# Naze32.net
KiCad netlist of a schematic drawn in EAGLE
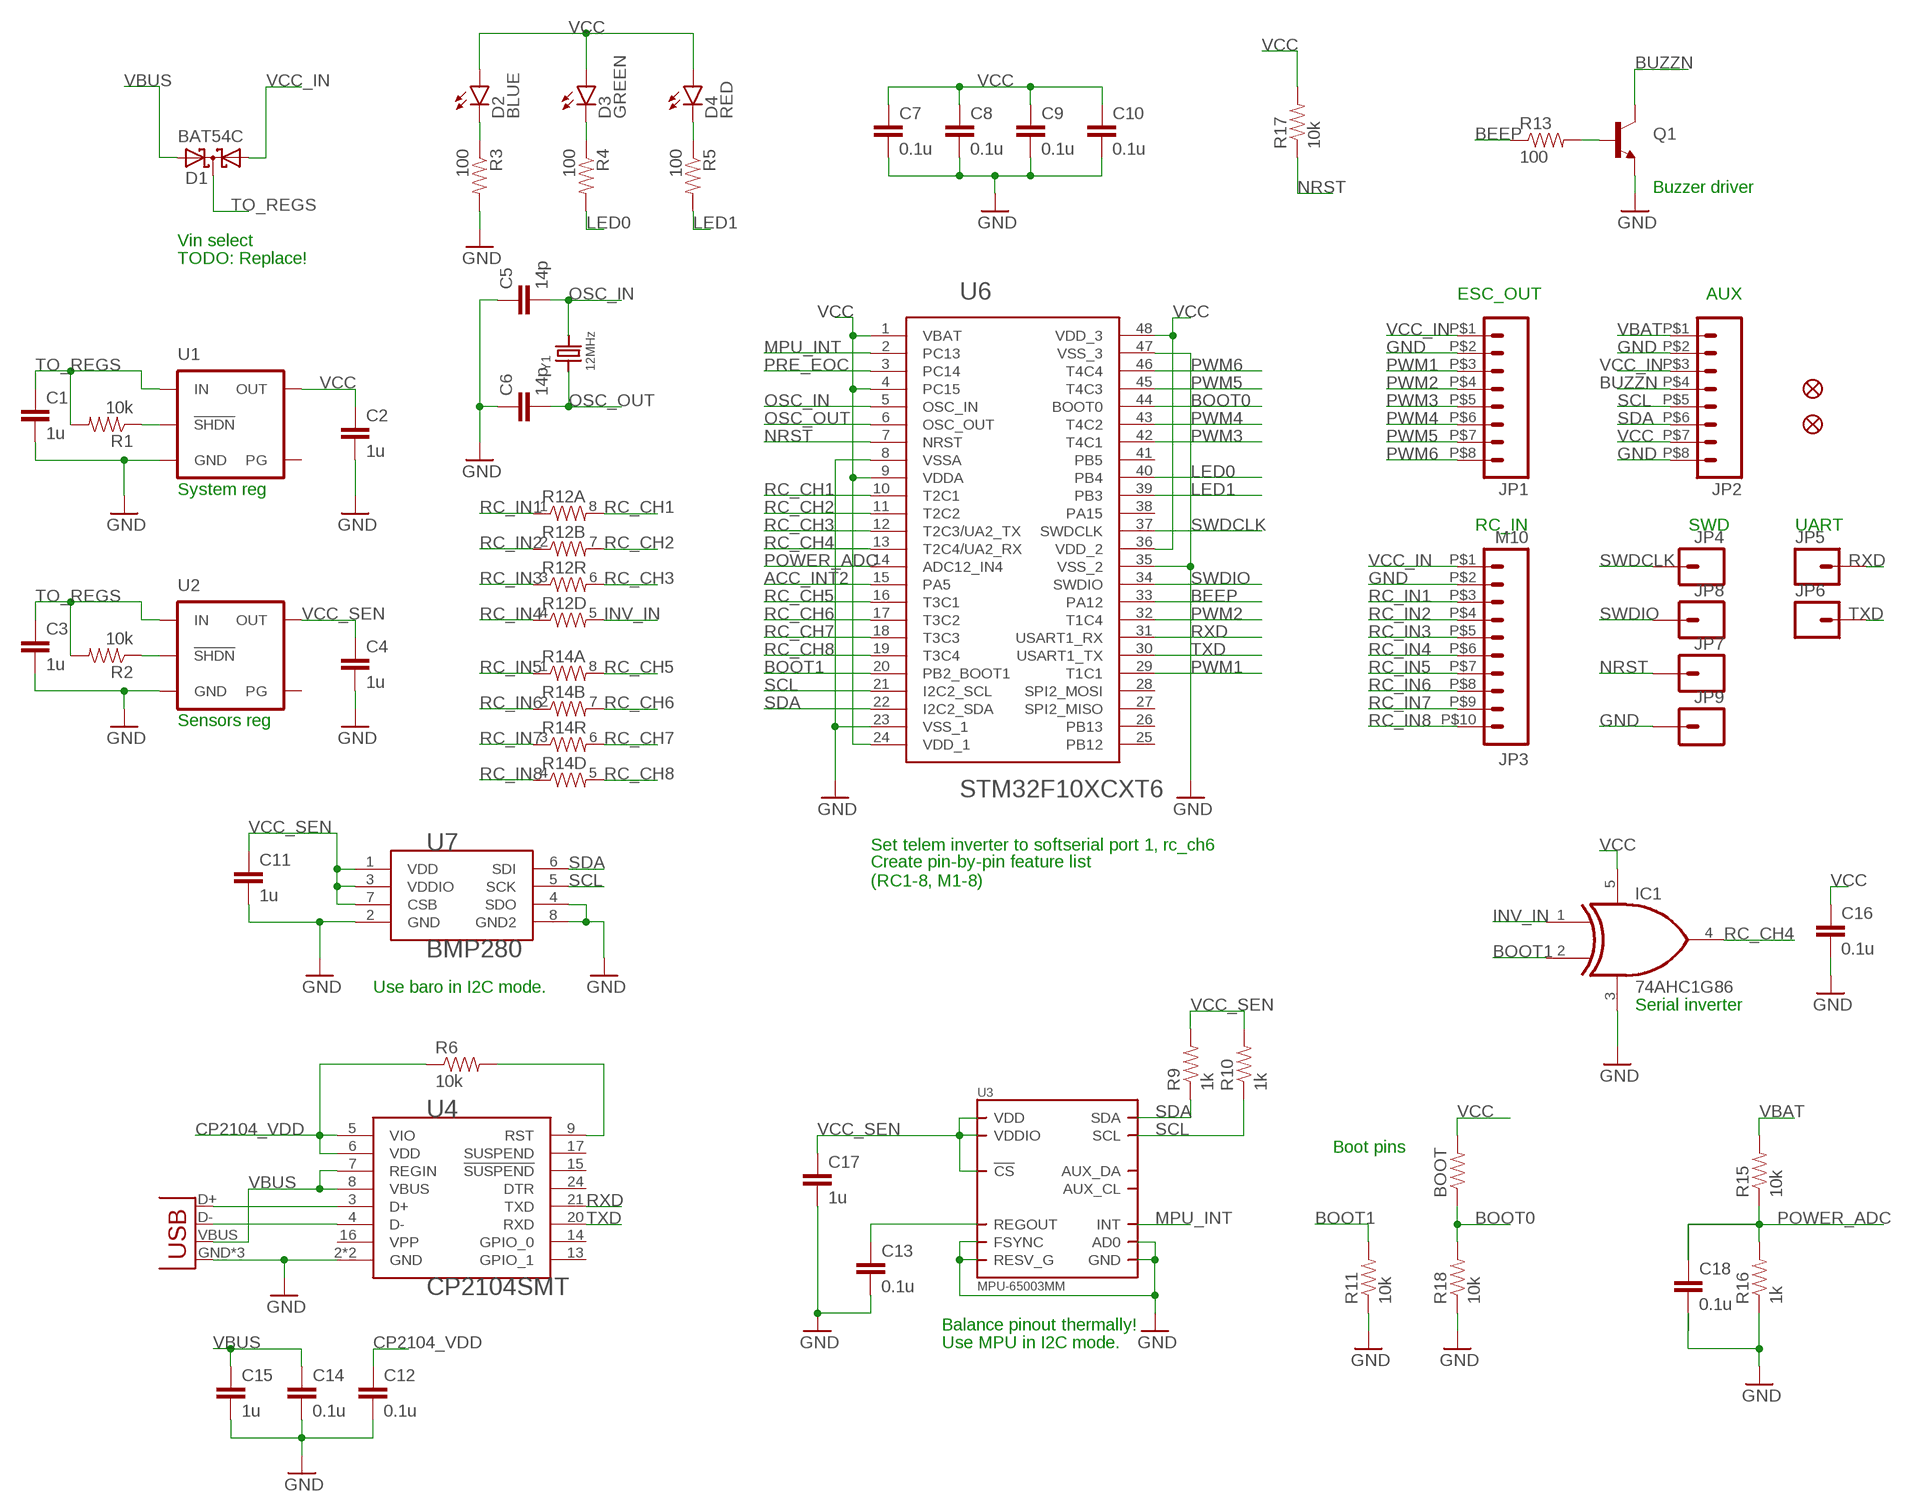
[diagram p0: schematic, sheet 1]

(export (version "E")
  (design (tool "Eeschema 10.0.6"))
  (components
    (comp (ref "BOOT")
      (value "RESISTOR0603")
      (footprint "eagle-import:0603-RES")
      (libsource (lib "eagle-import") (part "RESISTOR0603"))
    )
    (comp (ref "C1")
      (value "1u")
      (footprint "eagle-import:0402-CAP")
      (libsource (lib "eagle-import") (part "CAP0402-CAP"))
    )
    (comp (ref "C2")
      (value "1u")
      (footprint "eagle-import:0402-CAP")
      (libsource (lib "eagle-import") (part "CAP0402-CAP"))
    )
    (comp (ref "C3")
      (value "1u")
      (footprint "eagle-import:0402-CAP")
      (libsource (lib "eagle-import") (part "CAP0402-CAP"))
    )
    (comp (ref "C4")
      (value "1u")
      (footprint "eagle-import:0402-CAP")
      (libsource (lib "eagle-import") (part "CAP0402-CAP"))
    )
    (comp (ref "C5")
      (value "14p")
      (footprint "eagle-import:0402-CAP")
      (libsource (lib "eagle-import") (part "CAP0402-CAP"))
    )
    (comp (ref "C6")
      (value "14p")
      (footprint "eagle-import:0402-CAP")
      (libsource (lib "eagle-import") (part "CAP0402-CAP"))
    )
    (comp (ref "C7")
      (value "0.1u")
      (footprint "eagle-import:0402-CAP")
      (libsource (lib "eagle-import") (part "CAP0402-CAP"))
    )
    (comp (ref "C8")
      (value "0.1u")
      (footprint "eagle-import:0402-CAP")
      (libsource (lib "eagle-import") (part "CAP0402-CAP"))
    )
    (comp (ref "C9")
      (value "0.1u")
      (footprint "eagle-import:0402-CAP")
      (libsource (lib "eagle-import") (part "CAP0402-CAP"))
    )
    (comp (ref "C10")
      (value "0.1u")
      (footprint "eagle-import:0402-CAP")
      (libsource (lib "eagle-import") (part "CAP0402-CAP"))
    )
    (comp (ref "C11")
      (value "1u")
      (footprint "eagle-import:0402-CAP")
      (libsource (lib "eagle-import") (part "CAP0402-CAP"))
    )
    (comp (ref "C12")
      (value "0.1u")
      (footprint "eagle-import:0402-CAP")
      (libsource (lib "eagle-import") (part "CAP0402-CAP"))
    )
    (comp (ref "C13")
      (value "0.1u")
      (footprint "eagle-import:0402-CAP")
      (libsource (lib "eagle-import") (part "CAP0402-CAP"))
    )
    (comp (ref "C14")
      (value "0.1u")
      (footprint "eagle-import:0402-CAP")
      (libsource (lib "eagle-import") (part "CAP0402-CAP"))
    )
    (comp (ref "C15")
      (value "1u")
      (footprint "eagle-import:0402-CAP")
      (libsource (lib "eagle-import") (part "CAP0402-CAP"))
    )
    (comp (ref "C16")
      (value "0.1u")
      (footprint "eagle-import:0402-CAP")
      (libsource (lib "eagle-import") (part "CAP0402-CAP"))
    )
    (comp (ref "C17")
      (value "1u")
      (footprint "eagle-import:0402-CAP")
      (libsource (lib "eagle-import") (part "CAP0402-CAP"))
    )
    (comp (ref "C18")
      (value "0.1u")
      (footprint "eagle-import:0402-CAP")
      (libsource (lib "eagle-import") (part "CAP0402-CAP"))
    )
    (comp (ref "D1")
      (value "BAT54C")
      (footprint "eagle-import:SOT23")
      (libsource (lib "eagle-import") (part "BAT54C"))
    )
    (comp (ref "D2")
      (value "BLUE")
      (footprint "eagle-import:LED-0603")
      (libsource (lib "eagle-import") (part "LED-BLUE0603"))
    )
    (comp (ref "D3")
      (value "GREEN")
      (footprint "eagle-import:LED-0603")
      (libsource (lib "eagle-import") (part "LED-GREEN0603"))
    )
    (comp (ref "D4")
      (value "RED")
      (footprint "eagle-import:LED-0603")
      (libsource (lib "eagle-import") (part "LED-RED0603"))
    )
    (comp (ref "FID1")
      (value "FIDUCIALUFIDUCIAL")
      (footprint "eagle-import:MICRO-FIDUCIAL")
      (libsource (lib "eagle-import") (part "FIDUCIALUFIDUCIAL"))
    )
    (comp (ref "FID2")
      (value "FIDUCIALUFIDUCIAL")
      (footprint "eagle-import:MICRO-FIDUCIAL")
      (libsource (lib "eagle-import") (part "FIDUCIALUFIDUCIAL"))
    )
    (comp (ref "IC1")
      (value "74AHC1G86")
      (footprint "eagle-import:SC70-5")
      (libsource (lib "eagle-import") (part "741G86DCKAHC"))
    )
    (comp (ref "J1")
      (value "USB-MICROB")
      (footprint "eagle-import:USB-MICROB")
      (libsource (lib "eagle-import") (part "USB-MICROB"))
    )
    (comp (ref "JP1")
      (value "M08PAD-1X8")
      (footprint "eagle-import:PAD-1X8")
      (libsource (lib "eagle-import") (part "M08PAD-1X8"))
    )
    (comp (ref "JP2")
      (value "M08PAD-1X8")
      (footprint "eagle-import:PAD-1X8")
      (libsource (lib "eagle-import") (part "M08PAD-1X8"))
    )
    (comp (ref "JP3")
      (value "M10")
      (footprint "eagle-import:PAD_1X10")
      (libsource (lib "eagle-import") (part "M10"))
    )
    (comp (ref "JP4")
      (value "SCK")
      (footprint "eagle-import:PAD-ROUND")
      (libsource (lib "eagle-import") (part "M01ROUND"))
    )
    (comp (ref "JP5")
      (value "RX")
      (footprint "eagle-import:PAD-ROUND")
      (libsource (lib "eagle-import") (part "M01ROUND"))
    )
    (comp (ref "JP6")
      (value "TX")
      (footprint "eagle-import:PAD-ROUND")
      (libsource (lib "eagle-import") (part "M01ROUND"))
    )
    (comp (ref "JP7")
      (value "RST")
      (footprint "eagle-import:PAD-ROUND")
      (libsource (lib "eagle-import") (part "M01ROUND"))
    )
    (comp (ref "JP8")
      (value "IO")
      (footprint "eagle-import:PAD-ROUND")
      (libsource (lib "eagle-import") (part "M01ROUND"))
    )
    (comp (ref "JP9")
      (value "GND")
      (footprint "eagle-import:PAD-ROUND")
      (libsource (lib "eagle-import") (part "M01ROUND"))
    )
    (comp (ref "Q1")
      (value "TRANSISTOR_NPNSOT23")
      (footprint "eagle-import:SOT23")
      (libsource (lib "eagle-import") (part "TRANSISTOR_NPNSOT23"))
    )
    (comp (ref "R1")
      (value "10k")
      (footprint "eagle-import:0402-RES")
      (libsource (lib "eagle-import") (part "RESISTOR"))
    )
    (comp (ref "R2")
      (value "10k")
      (footprint "eagle-import:0402-RES")
      (libsource (lib "eagle-import") (part "RESISTOR"))
    )
    (comp (ref "R3")
      (value "100")
      (footprint "eagle-import:0402-RES")
      (libsource (lib "eagle-import") (part "RESISTOR"))
    )
    (comp (ref "R4")
      (value "100")
      (footprint "eagle-import:0402-RES")
      (libsource (lib "eagle-import") (part "RESISTOR"))
    )
    (comp (ref "R5")
      (value "100")
      (footprint "eagle-import:0402-RES")
      (libsource (lib "eagle-import") (part "RESISTOR"))
    )
    (comp (ref "R6")
      (value "10k")
      (footprint "eagle-import:0402-RES")
      (libsource (lib "eagle-import") (part "RESISTOR"))
    )
    (comp (ref "R9")
      (value "1k")
      (footprint "eagle-import:0402-RES")
      (libsource (lib "eagle-import") (part "RESISTOR"))
    )
    (comp (ref "R10")
      (value "1k")
      (footprint "eagle-import:0402-RES")
      (libsource (lib "eagle-import") (part "RESISTOR"))
    )
    (comp (ref "R11")
      (value "10k")
      (footprint "eagle-import:0402-RES")
      (libsource (lib "eagle-import") (part "RESISTOR"))
    )
    (comp (ref "R12")
      (value "RESISTOR-ARRAY0603-ARV")
      (footprint "eagle-import:0603-ARV")
      (libsource (lib "eagle-import") (part "RESISTOR-ARRAY0603-ARV"))
    )
    (comp (ref "R13")
      (value "100")
      (footprint "eagle-import:0402-RES")
      (libsource (lib "eagle-import") (part "RESISTOR"))
    )
    (comp (ref "R14")
      (value "RESISTOR-ARRAY0603-ARV")
      (footprint "eagle-import:0603-ARV")
      (libsource (lib "eagle-import") (part "RESISTOR-ARRAY0603-ARV"))
    )
    (comp (ref "R15")
      (value "10k")
      (footprint "eagle-import:0402-RES")
      (libsource (lib "eagle-import") (part "RESISTOR"))
    )
    (comp (ref "R16")
      (value "1k")
      (footprint "eagle-import:0402-RES")
      (libsource (lib "eagle-import") (part "RESISTOR"))
    )
    (comp (ref "R17")
      (value "10k")
      (footprint "eagle-import:0402-RES")
      (libsource (lib "eagle-import") (part "RESISTOR"))
    )
    (comp (ref "R18")
      (value "10k")
      (footprint "eagle-import:0402-RES")
      (libsource (lib "eagle-import") (part "RESISTOR"))
    )
    (comp (ref "U1")
      (value "MCP18243.3V")
      (footprint "eagle-import:SOT23-5")
      (libsource (lib "eagle-import") (part "MCP18243.3V"))
    )
    (comp (ref "U2")
      (value "MCP18243.3V")
      (footprint "eagle-import:SOT23-5")
      (libsource (lib "eagle-import") (part "MCP18243.3V"))
    )
    (comp (ref "U3")
      (value "MPU-65003MM")
      (footprint "eagle-import:QFN-24_3X3")
      (libsource (lib "eagle-import") (part "MPU-65003MM"))
    )
    (comp (ref "U4")
      (value "CP2104SMT")
      (footprint "eagle-import:QFN-24_ALT2")
      (libsource (lib "eagle-import") (part "CP2104SMT"))
    )
    (comp (ref "U6")
      (value "STM32F10XCXT6")
      (footprint "eagle-import:TQFP48")
      (libsource (lib "eagle-import") (part "STM32F10XCXT6"))
    )
    (comp (ref "U7")
      (value "BMP280")
      (footprint "eagle-import:LGA8")
      (libsource (lib "eagle-import") (part "BMP280"))
    )
    (comp (ref "Y1")
      (value "12MHz")
      (footprint "eagle-import:3.2X2.5MM")
      (libsource (lib "eagle-import") (part "CRYSTAL.3.2X2.5MM"))
    )
  )
  (nets
    (net (code "1") (name "/ACC_INT2") (class "Default")
      (node (ref "U6") (pin "15") (pinfunction "PA5_15") (pintype "bidirectional"))
    )
    (net (code "2") (name "/BEEP") (class "Default")
      (node (ref "R13") (pin "1") (pinfunction "1_1") (pintype "passive"))
      (node (ref "U6") (pin "33") (pinfunction "PA12_33") (pintype "bidirectional"))
    )
    (net (code "3") (name "/BOOT0") (class "Default")
      (node (ref "BOOT") (pin "1") (pinfunction "1_1") (pintype "passive"))
      (node (ref "R18") (pin "2") (pinfunction "2_2") (pintype "passive"))
      (node (ref "U6") (pin "44") (pinfunction "BOOT0_44") (pintype "bidirectional"))
    )
    (net (code "4") (name "/BOOT1") (class "Default")
      (node (ref "IC1") (pin "2") (pinfunction "I1_2") (pintype "input"))
      (node (ref "R11") (pin "2") (pinfunction "2_2") (pintype "passive"))
      (node (ref "U6") (pin "20") (pinfunction "PB2_BOOT1_20") (pintype "bidirectional"))
    )
    (net (code "5") (name "/BUZZN") (class "Default")
      (node (ref "JP2") (pin "P$4") (pinfunction "4_P$4") (pintype "passive"))
      (node (ref "Q1") (pin "3") (pinfunction "C_3") (pintype "passive"))
    )
    (net (code "6") (name "/CP2104_VDD") (class "Default")
      (node (ref "C12") (pin "1") (pinfunction "1_1") (pintype "passive"))
      (node (ref "R6") (pin "1") (pinfunction "1_1") (pintype "passive"))
      (node (ref "U4") (pin "5") (pinfunction "VIO_5") (pintype "bidirectional"))
      (node (ref "U4") (pin "6") (pinfunction "VDD_6") (pintype "bidirectional"))
    )
    (net (code "7") (name "/INV_IN") (class "Default")
      (node (ref "IC1") (pin "1") (pinfunction "I0_1") (pintype "input"))
      (node (ref "R12") (pin "5") (pinfunction "2_5") (pintype "passive"))
    )
    (net (code "8") (name "/LED0") (class "Default")
      (node (ref "R4") (pin "2") (pinfunction "2_2") (pintype "passive"))
      (node (ref "U6") (pin "40") (pinfunction "PB4_40") (pintype "bidirectional"))
    )
    (net (code "9") (name "/LED1") (class "Default")
      (node (ref "R5") (pin "2") (pinfunction "2_2") (pintype "passive"))
      (node (ref "U6") (pin "39") (pinfunction "PB3_39") (pintype "bidirectional"))
    )
    (net (code "10") (name "/MPU_INT") (class "Default")
      (node (ref "U3") (pin "12") (pinfunction "INT_12") (pintype "bidirectional"))
      (node (ref "U6") (pin "2") (pinfunction "PC13_2") (pintype "bidirectional"))
    )
    (net (code "11") (name "/NRST") (class "Default")
      (node (ref "JP7") (pin "P$1") (pinfunction "1_P$1") (pintype "passive"))
      (node (ref "R17") (pin "1") (pinfunction "1_1") (pintype "passive"))
      (node (ref "U6") (pin "7") (pinfunction "NRST_7") (pintype "bidirectional"))
    )
    (net (code "12") (name "/OSC_IN") (class "Default")
      (node (ref "C5") (pin "2") (pinfunction "2_2") (pintype "passive"))
      (node (ref "U6") (pin "5") (pinfunction "OSC_IN_5") (pintype "bidirectional"))
      (node (ref "Y1") (pin "3") (pinfunction "2_3") (pintype "passive"))
    )
    (net (code "13") (name "/OSC_OUT") (class "Default")
      (node (ref "C6") (pin "2") (pinfunction "2_2") (pintype "passive"))
      (node (ref "U6") (pin "6") (pinfunction "OSC_OUT_6") (pintype "bidirectional"))
      (node (ref "Y1") (pin "1") (pinfunction "1_1") (pintype "passive"))
    )
    (net (code "14") (name "/POWER_ADC") (class "Default")
      (node (ref "C18") (pin "1") (pinfunction "1_1") (pintype "passive"))
      (node (ref "R15") (pin "1") (pinfunction "1_1") (pintype "passive"))
      (node (ref "R16") (pin "2") (pinfunction "2_2") (pintype "passive"))
      (node (ref "U6") (pin "14") (pinfunction "ADC12_IN4_14") (pintype "bidirectional"))
    )
    (net (code "15") (name "/PRE_EOC") (class "Default")
      (node (ref "U6") (pin "3") (pinfunction "PC14_3") (pintype "bidirectional"))
    )
    (net (code "16") (name "/PWM1") (class "Default")
      (node (ref "JP1") (pin "P$3") (pinfunction "3_P$3") (pintype "passive"))
      (node (ref "U6") (pin "29") (pinfunction "T1C1_29") (pintype "bidirectional"))
    )
    (net (code "17") (name "/PWM2") (class "Default")
      (node (ref "JP1") (pin "P$4") (pinfunction "4_P$4") (pintype "passive"))
      (node (ref "U6") (pin "32") (pinfunction "T1C4_32") (pintype "bidirectional"))
    )
    (net (code "18") (name "/PWM3") (class "Default")
      (node (ref "JP1") (pin "P$5") (pinfunction "5_P$5") (pintype "passive"))
      (node (ref "U6") (pin "42") (pinfunction "T4C1_42") (pintype "bidirectional"))
    )
    (net (code "19") (name "/PWM4") (class "Default")
      (node (ref "JP1") (pin "P$6") (pinfunction "6_P$6") (pintype "passive"))
      (node (ref "U6") (pin "43") (pinfunction "T4C2_43") (pintype "bidirectional"))
    )
    (net (code "20") (name "/PWM5") (class "Default")
      (node (ref "JP1") (pin "P$7") (pinfunction "7_P$7") (pintype "passive"))
      (node (ref "U6") (pin "45") (pinfunction "T4C3_45") (pintype "bidirectional"))
    )
    (net (code "21") (name "/PWM6") (class "Default")
      (node (ref "JP1") (pin "P$8") (pinfunction "8_P$8") (pintype "passive"))
      (node (ref "U6") (pin "46") (pinfunction "T4C4_46") (pintype "bidirectional"))
    )
    (net (code "22") (name "/RC_CH1") (class "Default")
      (node (ref "R12") (pin "8") (pinfunction "2_8") (pintype "passive"))
      (node (ref "U6") (pin "10") (pinfunction "T2C1_10") (pintype "bidirectional"))
    )
    (net (code "23") (name "/RC_CH2") (class "Default")
      (node (ref "R12") (pin "7") (pinfunction "2_7") (pintype "passive"))
      (node (ref "U6") (pin "11") (pinfunction "T2C2_11") (pintype "bidirectional"))
    )
    (net (code "24") (name "/RC_CH3") (class "Default")
      (node (ref "R12") (pin "6") (pinfunction "2_6") (pintype "passive"))
      (node (ref "U6") (pin "12") (pinfunction "T2C3/UA2_TX_12") (pintype "bidirectional"))
    )
    (net (code "25") (name "/RC_CH4") (class "Default")
      (node (ref "IC1") (pin "4") (pinfunction "O_4") (pintype "output"))
      (node (ref "U6") (pin "13") (pinfunction "T2C4/UA2_RX_13") (pintype "bidirectional"))
    )
    (net (code "26") (name "/RC_CH5") (class "Default")
      (node (ref "R14") (pin "8") (pinfunction "2_8") (pintype "passive"))
      (node (ref "U6") (pin "16") (pinfunction "T3C1_16") (pintype "bidirectional"))
    )
    (net (code "27") (name "/RC_CH6") (class "Default")
      (node (ref "R14") (pin "7") (pinfunction "2_7") (pintype "passive"))
      (node (ref "U6") (pin "17") (pinfunction "T3C2_17") (pintype "bidirectional"))
    )
    (net (code "28") (name "/RC_CH7") (class "Default")
      (node (ref "R14") (pin "6") (pinfunction "2_6") (pintype "passive"))
      (node (ref "U6") (pin "18") (pinfunction "T3C3_18") (pintype "bidirectional"))
    )
    (net (code "29") (name "/RC_CH8") (class "Default")
      (node (ref "R14") (pin "5") (pinfunction "2_5") (pintype "passive"))
      (node (ref "U6") (pin "19") (pinfunction "T3C4_19") (pintype "bidirectional"))
    )
    (net (code "30") (name "/RC_IN1") (class "Default")
      (node (ref "JP3") (pin "P$3") (pinfunction "3_P$3") (pintype "passive"))
      (node (ref "R12") (pin "1") (pinfunction "1_1") (pintype "passive"))
    )
    (net (code "31") (name "/RC_IN2") (class "Default")
      (node (ref "JP3") (pin "P$4") (pinfunction "4_P$4") (pintype "passive"))
      (node (ref "R12") (pin "2") (pinfunction "1_2") (pintype "passive"))
    )
    (net (code "32") (name "/RC_IN3") (class "Default")
      (node (ref "JP3") (pin "P$5") (pinfunction "5_P$5") (pintype "passive"))
      (node (ref "R12") (pin "3") (pinfunction "1_3") (pintype "passive"))
    )
    (net (code "33") (name "/RC_IN4") (class "Default")
      (node (ref "JP3") (pin "P$6") (pinfunction "6_P$6") (pintype "passive"))
      (node (ref "R12") (pin "4") (pinfunction "1_4") (pintype "passive"))
    )
    (net (code "34") (name "/RC_IN5") (class "Default")
      (node (ref "JP3") (pin "P$7") (pinfunction "7_P$7") (pintype "passive"))
      (node (ref "R14") (pin "1") (pinfunction "1_1") (pintype "passive"))
    )
    (net (code "35") (name "/RC_IN6") (class "Default")
      (node (ref "JP3") (pin "P$8") (pinfunction "8_P$8") (pintype "passive"))
      (node (ref "R14") (pin "2") (pinfunction "1_2") (pintype "passive"))
    )
    (net (code "36") (name "/RC_IN7") (class "Default")
      (node (ref "JP3") (pin "P$9") (pinfunction "9_P$9") (pintype "passive"))
      (node (ref "R14") (pin "3") (pinfunction "1_3") (pintype "passive"))
    )
    (net (code "37") (name "/RC_IN8") (class "Default")
      (node (ref "JP3") (pin "P$10") (pinfunction "10_P$10") (pintype "passive"))
      (node (ref "R14") (pin "4") (pinfunction "1_4") (pintype "passive"))
    )
    (net (code "38") (name "/RXD") (class "Default")
      (node (ref "JP5") (pin "P$1") (pinfunction "1_P$1") (pintype "passive"))
      (node (ref "U4") (pin "21") (pinfunction "TXD_21") (pintype "bidirectional"))
      (node (ref "U6") (pin "31") (pinfunction "USART1_RX_31") (pintype "bidirectional"))
    )
    (net (code "39") (name "/SCL") (class "Default")
      (node (ref "JP2") (pin "P$5") (pinfunction "5_P$5") (pintype "passive"))
      (node (ref "R10") (pin "1") (pinfunction "1_1") (pintype "passive"))
      (node (ref "U3") (pin "23") (pinfunction "SCL_23") (pintype "bidirectional"))
      (node (ref "U6") (pin "21") (pinfunction "I2C2_SCL_21") (pintype "bidirectional"))
      (node (ref "U7") (pin "5") (pinfunction "SCK_5") (pintype "bidirectional"))
    )
    (net (code "40") (name "/SDA") (class "Default")
      (node (ref "JP2") (pin "P$6") (pinfunction "6_P$6") (pintype "passive"))
      (node (ref "R9") (pin "1") (pinfunction "1_1") (pintype "passive"))
      (node (ref "U3") (pin "24") (pinfunction "SDA_24") (pintype "bidirectional"))
      (node (ref "U6") (pin "22") (pinfunction "I2C2_SDA_22") (pintype "bidirectional"))
      (node (ref "U7") (pin "6") (pinfunction "SDI_6") (pintype "bidirectional"))
    )
    (net (code "41") (name "/SWDCLK") (class "Default")
      (node (ref "JP4") (pin "P$1") (pinfunction "1_P$1") (pintype "passive"))
      (node (ref "U6") (pin "37") (pinfunction "SWDCLK_37") (pintype "bidirectional"))
    )
    (net (code "42") (name "/SWDIO") (class "Default")
      (node (ref "JP8") (pin "P$1") (pinfunction "1_P$1") (pintype "passive"))
      (node (ref "U6") (pin "34") (pinfunction "SWDIO_34") (pintype "bidirectional"))
    )
    (net (code "43") (name "/TO_REGS") (class "Default")
      (node (ref "C1") (pin "1") (pinfunction "1_1") (pintype "passive"))
      (node (ref "C3") (pin "1") (pinfunction "1_1") (pintype "passive"))
      (node (ref "D1") (pin "3") (pinfunction "CC_3") (pintype "passive"))
      (node (ref "R1") (pin "2") (pinfunction "2_2") (pintype "passive"))
      (node (ref "R2") (pin "2") (pinfunction "2_2") (pintype "passive"))
      (node (ref "U1") (pin "1") (pinfunction "IN_1") (pintype "input"))
      (node (ref "U2") (pin "1") (pinfunction "IN_1") (pintype "input"))
    )
    (net (code "44") (name "/TXD") (class "Default")
      (node (ref "JP6") (pin "P$1") (pinfunction "1_P$1") (pintype "passive"))
      (node (ref "U4") (pin "20") (pinfunction "RXD_20") (pintype "bidirectional"))
      (node (ref "U6") (pin "30") (pinfunction "USART1_TX_30") (pintype "bidirectional"))
    )
    (net (code "45") (name "/VBAT") (class "Default")
      (node (ref "JP2") (pin "P$1") (pinfunction "1_P$1") (pintype "passive"))
      (node (ref "R15") (pin "2") (pinfunction "2_2") (pintype "passive"))
    )
    (net (code "46") (name "/VBUS") (class "Default")
      (node (ref "C14") (pin "1") (pinfunction "1_1") (pintype "passive"))
      (node (ref "C15") (pin "1") (pinfunction "1_1") (pintype "passive"))
      (node (ref "D1") (pin "2") (pinfunction "A2_2") (pintype "passive"))
      (node (ref "J1") (pin "VBUS") (pinfunction "VBUS_VBUS") (pintype "bidirectional"))
      (node (ref "U4") (pin "7") (pinfunction "REGIN_7") (pintype "bidirectional"))
      (node (ref "U4") (pin "8") (pinfunction "VBUS_8") (pintype "bidirectional"))
    )
    (net (code "47") (name "/VCC") (class "Default")
      (node (ref "BOOT") (pin "2") (pinfunction "2_2") (pintype "passive"))
      (node (ref "C10") (pin "1") (pinfunction "1_1") (pintype "passive"))
      (node (ref "C16") (pin "1") (pinfunction "1_1") (pintype "passive"))
      (node (ref "C2") (pin "1") (pinfunction "1_1") (pintype "passive"))
      (node (ref "C7") (pin "1") (pinfunction "1_1") (pintype "passive"))
      (node (ref "C8") (pin "1") (pinfunction "1_1") (pintype "passive"))
      (node (ref "C9") (pin "1") (pinfunction "1_1") (pintype "passive"))
      (node (ref "D2") (pin "A") (pinfunction "A_A") (pintype "passive"))
      (node (ref "D3") (pin "A") (pinfunction "A_A") (pintype "passive"))
      (node (ref "D4") (pin "A") (pinfunction "A_A") (pintype "passive"))
      (node (ref "IC1") (pin "5") (pinfunction "VCC_5") (pintype "power_in"))
      (node (ref "JP2") (pin "P$7") (pinfunction "7_P$7") (pintype "passive"))
      (node (ref "R17") (pin "2") (pinfunction "2_2") (pintype "passive"))
      (node (ref "U1") (pin "5") (pinfunction "OUT_5") (pintype "passive"))
      (node (ref "U6") (pin "1") (pinfunction "VBAT_1") (pintype "bidirectional"))
      (node (ref "U6") (pin "24") (pinfunction "VDD_1_24") (pintype "bidirectional"))
      (node (ref "U6") (pin "36") (pinfunction "VDD_2_36") (pintype "bidirectional"))
      (node (ref "U6") (pin "4") (pinfunction "PC15_4") (pintype "bidirectional"))
      (node (ref "U6") (pin "48") (pinfunction "VDD_3_48") (pintype "bidirectional"))
      (node (ref "U6") (pin "9") (pinfunction "VDDA_9") (pintype "bidirectional"))
    )
    (net (code "48") (name "/VCC_IN") (class "Default")
      (node (ref "D1") (pin "1") (pinfunction "A1_1") (pintype "passive"))
      (node (ref "JP1") (pin "P$1") (pinfunction "1_P$1") (pintype "passive"))
      (node (ref "JP2") (pin "P$3") (pinfunction "3_P$3") (pintype "passive"))
      (node (ref "JP3") (pin "P$1") (pinfunction "1_P$1") (pintype "passive"))
    )
    (net (code "49") (name "/VCC_SEN") (class "Default")
      (node (ref "C11") (pin "1") (pinfunction "1_1") (pintype "passive"))
      (node (ref "C17") (pin "1") (pinfunction "1_1") (pintype "passive"))
      (node (ref "C4") (pin "1") (pinfunction "1_1") (pintype "passive"))
      (node (ref "R10") (pin "2") (pinfunction "2_2") (pintype "passive"))
      (node (ref "R9") (pin "2") (pinfunction "2_2") (pintype "passive"))
      (node (ref "U2") (pin "5") (pinfunction "OUT_5") (pintype "passive"))
      (node (ref "U3") (pin "13") (pinfunction "VDD_13") (pintype "bidirectional"))
      (node (ref "U3") (pin "22") (pinfunction "~{CS}_22") (pintype "bidirectional"))
      (node (ref "U3") (pin "8") (pinfunction "VDDIO_8") (pintype "bidirectional"))
      (node (ref "U7") (pin "1") (pinfunction "VDD_1") (pintype "bidirectional"))
      (node (ref "U7") (pin "3") (pinfunction "VDDIO_3") (pintype "bidirectional"))
      (node (ref "U7") (pin "7") (pinfunction "CSB_7") (pintype "bidirectional"))
    )
    (net (code "50") (name "GND") (class "Default")
      (node (ref "C1") (pin "2") (pinfunction "2_2") (pintype "passive"))
      (node (ref "C10") (pin "2") (pinfunction "2_2") (pintype "passive"))
      (node (ref "C11") (pin "2") (pinfunction "2_2") (pintype "passive"))
      (node (ref "C12") (pin "2") (pinfunction "2_2") (pintype "passive"))
      (node (ref "C13") (pin "2") (pinfunction "2_2") (pintype "passive"))
      (node (ref "C14") (pin "2") (pinfunction "2_2") (pintype "passive"))
      (node (ref "C15") (pin "2") (pinfunction "2_2") (pintype "passive"))
      (node (ref "C16") (pin "2") (pinfunction "2_2") (pintype "passive"))
      (node (ref "C17") (pin "2") (pinfunction "2_2") (pintype "passive"))
      (node (ref "C18") (pin "2") (pinfunction "2_2") (pintype "passive"))
      (node (ref "C2") (pin "2") (pinfunction "2_2") (pintype "passive"))
      (node (ref "C3") (pin "2") (pinfunction "2_2") (pintype "passive"))
      (node (ref "C4") (pin "2") (pinfunction "2_2") (pintype "passive"))
      (node (ref "C5") (pin "1") (pinfunction "1_1") (pintype "passive"))
      (node (ref "C6") (pin "1") (pinfunction "1_1") (pintype "passive"))
      (node (ref "C7") (pin "2") (pinfunction "2_2") (pintype "passive"))
      (node (ref "C8") (pin "2") (pinfunction "2_2") (pintype "passive"))
      (node (ref "C9") (pin "2") (pinfunction "2_2") (pintype "passive"))
      (node (ref "IC1") (pin "3") (pinfunction "GND_3") (pintype "power_in"))
      (node (ref "J1") (pin "GND") (pinfunction "GND_GND") (pintype "bidirectional"))
      (node (ref "J1") (pin "MT1") (pinfunction "GND_MT1") (pintype "bidirectional"))
      (node (ref "J1") (pin "MT2") (pinfunction "GND_MT2") (pintype "bidirectional"))
      (node (ref "JP1") (pin "P$2") (pinfunction "2_P$2") (pintype "passive"))
      (node (ref "JP2") (pin "P$2") (pinfunction "2_P$2") (pintype "passive"))
      (node (ref "JP2") (pin "P$8") (pinfunction "8_P$8") (pintype "passive"))
      (node (ref "JP3") (pin "P$2") (pinfunction "2_P$2") (pintype "passive"))
      (node (ref "JP9") (pin "P$1") (pinfunction "1_P$1") (pintype "passive"))
      (node (ref "Q1") (pin "2") (pinfunction "E_2") (pintype "passive"))
      (node (ref "R11") (pin "1") (pinfunction "1_1") (pintype "passive"))
      (node (ref "R16") (pin "1") (pinfunction "1_1") (pintype "passive"))
      (node (ref "R18") (pin "1") (pinfunction "1_1") (pintype "passive"))
      (node (ref "R3") (pin "2") (pinfunction "2_2") (pintype "passive"))
      (node (ref "U1") (pin "2") (pinfunction "GND_2") (pintype "input"))
      (node (ref "U2") (pin "2") (pinfunction "GND_2") (pintype "input"))
      (node (ref "U3") (pin "11") (pinfunction "FSYNC_11") (pintype "bidirectional"))
      (node (ref "U3") (pin "18") (pinfunction "GND_18") (pintype "bidirectional"))
      (node (ref "U3") (pin "20") (pinfunction "RESV_G_20") (pintype "bidirectional"))
      (node (ref "U3") (pin "9") (pinfunction "AD0_9") (pintype "bidirectional"))
      (node (ref "U4") (pin "2") (pinfunction "GND_2") (pintype "bidirectional"))
      (node (ref "U4") (pin "EP") (pinfunction "GND_EP") (pintype "bidirectional"))
      (node (ref "U6") (pin "23") (pinfunction "VSS_1_23") (pintype "bidirectional"))
      (node (ref "U6") (pin "35") (pinfunction "VSS_2_35") (pintype "bidirectional"))
      (node (ref "U6") (pin "47") (pinfunction "VSS_3_47") (pintype "bidirectional"))
      (node (ref "U6") (pin "8") (pinfunction "VSSA_8") (pintype "bidirectional"))
      (node (ref "U7") (pin "2") (pinfunction "GND_2") (pintype "bidirectional"))
      (node (ref "U7") (pin "4") (pinfunction "SDO_4") (pintype "bidirectional"))
      (node (ref "U7") (pin "8") (pinfunction "GND2_8") (pintype "bidirectional"))
    )
    (net (code "51") (name "Net-(D2-PadC)") (class "Default")
      (node (ref "D2") (pin "C") (pinfunction "C_C") (pintype "passive"))
      (node (ref "R3") (pin "1") (pinfunction "1_1") (pintype "passive"))
    )
    (net (code "52") (name "Net-(D3-PadC)") (class "Default")
      (node (ref "D3") (pin "C") (pinfunction "C_C") (pintype "passive"))
      (node (ref "R4") (pin "1") (pinfunction "1_1") (pintype "passive"))
    )
    (net (code "53") (name "Net-(D4-PadC)") (class "Default")
      (node (ref "D4") (pin "C") (pinfunction "C_C") (pintype "passive"))
      (node (ref "R5") (pin "1") (pinfunction "1_1") (pintype "passive"))
    )
    (net (code "54") (name "Net-(Q1-B)") (class "Default")
      (node (ref "Q1") (pin "1") (pinfunction "B_1") (pintype "passive"))
      (node (ref "R13") (pin "2") (pinfunction "2_2") (pintype "passive"))
    )
    (net (code "55") (name "Net-(U1-~{SHDN})") (class "Default")
      (node (ref "R1") (pin "1") (pinfunction "1_1") (pintype "passive"))
      (node (ref "U1") (pin "3") (pinfunction "~{SHDN}_3") (pintype "input"))
    )
    (net (code "56") (name "Net-(U2-~{SHDN})") (class "Default")
      (node (ref "R2") (pin "1") (pinfunction "1_1") (pintype "passive"))
      (node (ref "U2") (pin "3") (pinfunction "~{SHDN}_3") (pintype "input"))
    )
    (net (code "57") (name "Net-(U3-REGOUT)") (class "Default")
      (node (ref "C13") (pin "1") (pinfunction "1_1") (pintype "passive"))
      (node (ref "U3") (pin "10") (pinfunction "REGOUT_10") (pintype "bidirectional"))
    )
    (net (code "58") (name "Net-(U4-D+)") (class "Default")
      (node (ref "J1") (pin "D+") (pinfunction "D+_D+") (pintype "bidirectional"))
      (node (ref "U4") (pin "3") (pinfunction "D+_3") (pintype "bidirectional"))
    )
    (net (code "59") (name "Net-(U4-D-)") (class "Default")
      (node (ref "J1") (pin "D-") (pinfunction "D-_D-") (pintype "bidirectional"))
      (node (ref "U4") (pin "4") (pinfunction "D-_4") (pintype "bidirectional"))
    )
    (net (code "60") (name "Net-(U4-RST)") (class "Default")
      (node (ref "R6") (pin "2") (pinfunction "2_2") (pintype "passive"))
      (node (ref "U4") (pin "9") (pinfunction "RST_9") (pintype "bidirectional"))
    )
    (net (code "61") (name "unconnected-(U1-PG-Pad4)") (class "Default")
      (node (ref "U1") (pin "4") (pinfunction "PG_4") (pintype "input"))
    )
    (net (code "62") (name "unconnected-(U2-PG-Pad4)") (class "Default")
      (node (ref "U2") (pin "4") (pinfunction "PG_4") (pintype "input"))
    )
    (net (code "63") (name "unconnected-(U3-AUX_CL-Pad7)") (class "Default")
      (node (ref "U3") (pin "7") (pinfunction "AUX_CL_7") (pintype "bidirectional"))
    )
    (net (code "64") (name "unconnected-(U3-AUX_DA-Pad21)") (class "Default")
      (node (ref "U3") (pin "21") (pinfunction "AUX_DA_21") (pintype "bidirectional"))
    )
    (net (code "65") (name "unconnected-(U4-DTR-Pad24)") (class "Default")
      (node (ref "U4") (pin "24") (pinfunction "DTR_24") (pintype "bidirectional"))
    )
    (net (code "66") (name "unconnected-(U4-GPIO_0-Pad14)") (class "Default")
      (node (ref "U4") (pin "14") (pinfunction "GPIO_0_14") (pintype "bidirectional"))
    )
    (net (code "67") (name "unconnected-(U4-GPIO_1-Pad13)") (class "Default")
      (node (ref "U4") (pin "13") (pinfunction "GPIO_1_13") (pintype "bidirectional"))
    )
    (net (code "68") (name "unconnected-(U4-SUSPEND-Pad17)") (class "Default")
      (node (ref "U4") (pin "17") (pinfunction "SUSPEND_17") (pintype "bidirectional"))
    )
    (net (code "69") (name "unconnected-(U4-VPP-Pad16)") (class "Default")
      (node (ref "U4") (pin "16") (pinfunction "VPP_16") (pintype "bidirectional"))
    )
    (net (code "70") (name "unconnected-(U4-~{SUSPEND}-Pad15)") (class "Default")
      (node (ref "U4") (pin "15") (pinfunction "~{SUSPEND}_15") (pintype "bidirectional"))
    )
    (net (code "71") (name "unconnected-(U6-PA15-Pad38)") (class "Default")
      (node (ref "U6") (pin "38") (pinfunction "PA15_38") (pintype "bidirectional"))
    )
    (net (code "72") (name "unconnected-(U6-PB5-Pad41)") (class "Default")
      (node (ref "U6") (pin "41") (pinfunction "PB5_41") (pintype "bidirectional"))
    )
    (net (code "73") (name "unconnected-(U6-PB12-Pad25)") (class "Default")
      (node (ref "U6") (pin "25") (pinfunction "PB12_25") (pintype "bidirectional"))
    )
    (net (code "74") (name "unconnected-(U6-PB13-Pad26)") (class "Default")
      (node (ref "U6") (pin "26") (pinfunction "PB13_26") (pintype "bidirectional"))
    )
    (net (code "75") (name "unconnected-(U6-SPI2_MISO-Pad27)") (class "Default")
      (node (ref "U6") (pin "27") (pinfunction "SPI2_MISO_27") (pintype "bidirectional"))
    )
    (net (code "76") (name "unconnected-(U6-SPI2_MOSI-Pad28)") (class "Default")
      (node (ref "U6") (pin "28") (pinfunction "SPI2_MOSI_28") (pintype "bidirectional"))
    )
  )
)
